# bldc-driver.net
KiCad netlist of a schematic drawn in Altium Designer
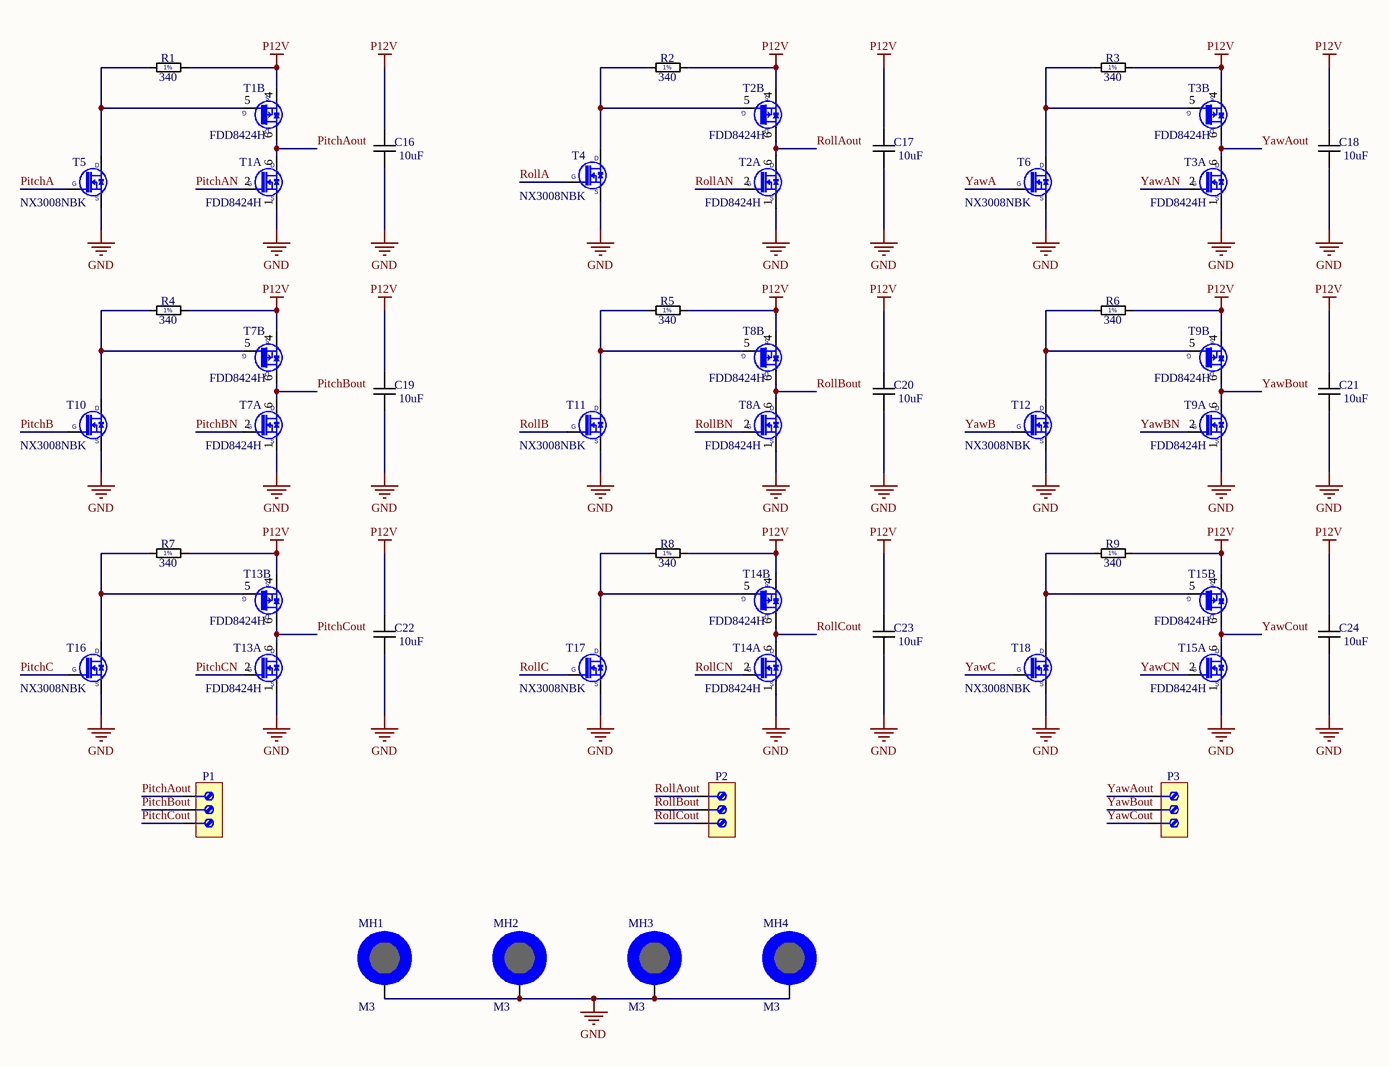
[diagram p0: bldc-driver.SchDoc]

(export (version "E")
  (design (tool "Eeschema 10.0.6"))
  (components
    (comp (ref "C16")
      (value "10uF")
      (footprint "CAPC0603X90N")
      (description "Non-polarised capacitor")
      (fields
        (field (name "MANUFACTURER") "GENERIC")
        (field (name "MANUFACTURER PART NUMBER") "CC0603_10UF_16V_20%_X5R")
        (field (name "AUTHOR") "KB")
      )
      (libsource (lib "Capacitors") (part "Capacitor - non polarized"))
    )
    (comp (ref "C17")
      (value "10uF")
      (footprint "CAPC0603X90N")
      (description "Non-polarised capacitor")
      (fields
        (field (name "MANUFACTURER") "GENERIC")
        (field (name "MANUFACTURER PART NUMBER") "CC0603_10UF_16V_20%_X5R")
        (field (name "AUTHOR") "KB")
      )
      (libsource (lib "Capacitors") (part "Capacitor - non polarized"))
    )
    (comp (ref "C18")
      (value "10uF")
      (footprint "CAPC0603X90N")
      (description "Non-polarised capacitor")
      (fields
        (field (name "MANUFACTURER") "GENERIC")
        (field (name "MANUFACTURER PART NUMBER") "CC0603_10UF_16V_20%_X5R")
        (field (name "AUTHOR") "KB")
      )
      (libsource (lib "Capacitors") (part "Capacitor - non polarized"))
    )
    (comp (ref "C19")
      (value "10uF")
      (footprint "CAPC0603X90N")
      (description "Non-polarised capacitor")
      (fields
        (field (name "MANUFACTURER") "GENERIC")
        (field (name "MANUFACTURER PART NUMBER") "CC0603_10UF_16V_20%_X5R")
        (field (name "AUTHOR") "KB")
      )
      (libsource (lib "Capacitors") (part "Capacitor - non polarized"))
    )
    (comp (ref "C20")
      (value "10uF")
      (footprint "CAPC0603X90N")
      (description "Non-polarised capacitor")
      (fields
        (field (name "MANUFACTURER") "GENERIC")
        (field (name "MANUFACTURER PART NUMBER") "CC0603_10UF_16V_20%_X5R")
        (field (name "AUTHOR") "KB")
      )
      (libsource (lib "Capacitors") (part "Capacitor - non polarized"))
    )
    (comp (ref "C21")
      (value "10uF")
      (footprint "CAPC0603X90N")
      (description "Non-polarised capacitor")
      (fields
        (field (name "MANUFACTURER") "GENERIC")
        (field (name "MANUFACTURER PART NUMBER") "CC0603_10UF_16V_20%_X5R")
        (field (name "AUTHOR") "KB")
      )
      (libsource (lib "Capacitors") (part "Capacitor - non polarized"))
    )
    (comp (ref "C22")
      (value "10uF")
      (footprint "CAPC0603X90N")
      (description "Non-polarised capacitor")
      (fields
        (field (name "MANUFACTURER") "GENERIC")
        (field (name "MANUFACTURER PART NUMBER") "CC0603_10UF_16V_20%_X5R")
        (field (name "AUTHOR") "KB")
      )
      (libsource (lib "Capacitors") (part "Capacitor - non polarized"))
    )
    (comp (ref "C23")
      (value "10uF")
      (footprint "CAPC0603X90N")
      (description "Non-polarised capacitor")
      (fields
        (field (name "MANUFACTURER") "GENERIC")
        (field (name "MANUFACTURER PART NUMBER") "CC0603_10UF_16V_20%_X5R")
        (field (name "AUTHOR") "KB")
      )
      (libsource (lib "Capacitors") (part "Capacitor - non polarized"))
    )
    (comp (ref "C24")
      (value "10uF")
      (footprint "CAPC0603X90N")
      (description "Non-polarised capacitor")
      (fields
        (field (name "MANUFACTURER") "GENERIC")
        (field (name "MANUFACTURER PART NUMBER") "CC0603_10UF_16V_20%_X5R")
        (field (name "AUTHOR") "KB")
      )
      (libsource (lib "Capacitors") (part "Capacitor - non polarized"))
    )
    (comp (ref "MH1")
      (value "M3")
      (footprint "MH-M3_COPPER")
      (description "Mounting hole, M3, exposed pad")
      (fields (field (name "AUTHOR") "KB"))
      (libsource (lib "Mechanical And PCB Features") (part "MH"))
    )
    (comp (ref "MH2")
      (value "M3")
      (footprint "MH-M3_COPPER")
      (description "Mounting hole, M3, exposed pad")
      (fields (field (name "AUTHOR") "KB"))
      (libsource (lib "Mechanical And PCB Features") (part "MH"))
    )
    (comp (ref "MH3")
      (value "M3")
      (footprint "MH-M3_COPPER")
      (description "Mounting hole, M3, exposed pad")
      (fields (field (name "AUTHOR") "KB"))
      (libsource (lib "Mechanical And PCB Features") (part "MH"))
    )
    (comp (ref "MH4")
      (value "M3")
      (footprint "MH-M3_COPPER")
      (description "Mounting hole, M3, exposed pad")
      (fields (field (name "AUTHOR") "KB"))
      (libsource (lib "Mechanical And PCB Features") (part "MH"))
    )
    (comp (ref "P1")
      (value "AK100/..DS-5.0-V-GREY")
      (footprint "SCREWERM_THT_3X1H_5P08MM")
      (description "Terminal Block, Right angle, 3 Positions, THT, Screw Connection, 15x9mm body")
      (fields
        (field (name "MANUFACTURER") "GENERIC")
        (field (name "MANUFACTURER PART NUMBER") "SCREWTERM_THT_3X1H_5P08MM")
        (field (name "AUTHOR") "KB")
      )
      (libsource (lib "Connectors") (part "Terminal Block_3 Positions_Screw Connection"))
    )
    (comp (ref "P2")
      (value "AK100/..DS-5.0-V-GREY")
      (footprint "SCREWERM_THT_3X1H_5P08MM")
      (description "Terminal Block, Right angle, 3 Positions, THT, Screw Connection, 15x9mm body")
      (fields
        (field (name "MANUFACTURER") "GENERIC")
        (field (name "MANUFACTURER PART NUMBER") "SCREWTERM_THT_3X1H_5P08MM")
        (field (name "AUTHOR") "KB")
      )
      (libsource (lib "Connectors") (part "Terminal Block_3 Positions_Screw Connection"))
    )
    (comp (ref "P3")
      (value "AK100/..DS-5.0-V-GREY")
      (footprint "SCREWERM_THT_3X1H_5P08MM")
      (description "Terminal Block, Right angle, 3 Positions, THT, Screw Connection, 15x9mm body")
      (fields
        (field (name "MANUFACTURER") "GENERIC")
        (field (name "MANUFACTURER PART NUMBER") "SCREWTERM_THT_3X1H_5P08MM")
        (field (name "AUTHOR") "KB")
      )
      (libsource (lib "Connectors") (part "Terminal Block_3 Positions_Screw Connection"))
    )
    (comp (ref "R1")
      (value "340")
      (footprint "RESC0402X40N")
      (description "General Purpose Thick Film Chip Resistor")
      (fields
        (field (name "MANUFACTURER") "GENERIC")
        (field (name "MANUFACTURER PART NUMBER") "R0402_340R_0.0625W 0.1W 0.125W 0.25W 0.5W 1W 0.75W 1W_100PPM")
        (field (name "AUTHOR") "KB")
      )
      (libsource (lib "Resistors") (part "Resistor - 1%"))
    )
    (comp (ref "R2")
      (value "340")
      (footprint "RESC0402X40N")
      (description "General Purpose Thick Film Chip Resistor")
      (fields
        (field (name "MANUFACTURER") "GENERIC")
        (field (name "MANUFACTURER PART NUMBER") "R0402_340R_0.0625W 0.1W 0.125W 0.25W 0.5W 1W 0.75W 1W_100PPM")
        (field (name "AUTHOR") "KB")
      )
      (libsource (lib "Resistors") (part "Resistor - 1%"))
    )
    (comp (ref "R3")
      (value "340")
      (footprint "RESC0402X40N")
      (description "General Purpose Thick Film Chip Resistor")
      (fields
        (field (name "MANUFACTURER") "GENERIC")
        (field (name "MANUFACTURER PART NUMBER") "R0402_340R_0.0625W 0.1W 0.125W 0.25W 0.5W 1W 0.75W 1W_100PPM")
        (field (name "AUTHOR") "KB")
      )
      (libsource (lib "Resistors") (part "Resistor - 1%"))
    )
    (comp (ref "R4")
      (value "340")
      (footprint "RESC0402X40N")
      (description "General Purpose Thick Film Chip Resistor")
      (fields
        (field (name "MANUFACTURER") "GENERIC")
        (field (name "MANUFACTURER PART NUMBER") "R0402_340R_0.0625W 0.1W 0.125W 0.25W 0.5W 1W 0.75W 1W_100PPM")
        (field (name "AUTHOR") "KB")
      )
      (libsource (lib "Resistors") (part "Resistor - 1%"))
    )
    (comp (ref "R5")
      (value "340")
      (footprint "RESC0402X40N")
      (description "General Purpose Thick Film Chip Resistor")
      (fields
        (field (name "MANUFACTURER") "GENERIC")
        (field (name "MANUFACTURER PART NUMBER") "R0402_340R_0.0625W 0.1W 0.125W 0.25W 0.5W 1W 0.75W 1W_100PPM")
        (field (name "AUTHOR") "KB")
      )
      (libsource (lib "Resistors") (part "Resistor - 1%"))
    )
    (comp (ref "R6")
      (value "340")
      (footprint "RESC0402X40N")
      (description "General Purpose Thick Film Chip Resistor")
      (fields
        (field (name "MANUFACTURER") "GENERIC")
        (field (name "MANUFACTURER PART NUMBER") "R0402_340R_0.0625W 0.1W 0.125W 0.25W 0.5W 1W 0.75W 1W_100PPM")
        (field (name "AUTHOR") "KB")
      )
      (libsource (lib "Resistors") (part "Resistor - 1%"))
    )
    (comp (ref "R7")
      (value "340")
      (footprint "RESC0402X40N")
      (description "General Purpose Thick Film Chip Resistor")
      (fields
        (field (name "MANUFACTURER") "GENERIC")
        (field (name "MANUFACTURER PART NUMBER") "R0402_340R_0.0625W 0.1W 0.125W 0.25W 0.5W 1W 0.75W 1W_100PPM")
        (field (name "AUTHOR") "KB")
      )
      (libsource (lib "Resistors") (part "Resistor - 1%"))
    )
    (comp (ref "R8")
      (value "340")
      (footprint "RESC0402X40N")
      (description "General Purpose Thick Film Chip Resistor")
      (fields
        (field (name "MANUFACTURER") "GENERIC")
        (field (name "MANUFACTURER PART NUMBER") "R0402_340R_0.0625W 0.1W 0.125W 0.25W 0.5W 1W 0.75W 1W_100PPM")
        (field (name "AUTHOR") "KB")
      )
      (libsource (lib "Resistors") (part "Resistor - 1%"))
    )
    (comp (ref "R9")
      (value "340")
      (footprint "RESC0402X40N")
      (description "General Purpose Thick Film Chip Resistor")
      (fields
        (field (name "MANUFACTURER") "GENERIC")
        (field (name "MANUFACTURER PART NUMBER") "R0402_340R_0.0625W 0.1W 0.125W 0.25W 0.5W 1W 0.75W 1W_100PPM")
        (field (name "AUTHOR") "KB")
      )
      (libsource (lib "Resistors") (part "Resistor - 1%"))
    )
    (comp (ref "T1")
      (value "FDD8424H")
      (footprint "TO252 - 4L")
      (fields (field (name "AUTHOR") "PC"))
      (libsource (lib "ICs And Semiconductors") (part "FDD8424H"))
    )
    (comp (ref "T2")
      (value "FDD8424H")
      (footprint "TO252 - 4L")
      (fields (field (name "AUTHOR") "PC"))
      (libsource (lib "ICs And Semiconductors") (part "FDD8424H"))
    )
    (comp (ref "T3")
      (value "FDD8424H")
      (footprint "TO252 - 4L")
      (fields (field (name "AUTHOR") "PC"))
      (libsource (lib "") (part "FDD8424H_1"))
    )
    (comp (ref "T4")
      (value "NX3008NBK")
      (footprint "SOT23-3")
      (description "30 V, 400 mA N-channel Trench MOSFET")
      (fields (field (name "AUTHOR") "PC"))
      (libsource (lib "ICs And Semiconductors") (part "N-MOSFET-D 1G 2S 3D"))
    )
    (comp (ref "T5")
      (value "NX3008NBK")
      (footprint "SOT23-3")
      (description "30 V, 400 mA N-channel Trench MOSFET")
      (fields (field (name "AUTHOR") "PC"))
      (libsource (lib "ICs And Semiconductors") (part "N-MOSFET-D 1G 2S 3D"))
    )
    (comp (ref "T6")
      (value "NX3008NBK")
      (footprint "SOT23-3")
      (description "30 V, 400 mA N-channel Trench MOSFET")
      (fields (field (name "AUTHOR") "PC"))
      (libsource (lib "ICs And Semiconductors") (part "N-MOSFET-D 1G 2S 3D"))
    )
    (comp (ref "T7")
      (value "FDD8424H")
      (footprint "TO252 - 4L")
      (fields (field (name "AUTHOR") "PC"))
      (libsource (lib "ICs And Semiconductors") (part "FDD8424H"))
    )
    (comp (ref "T8")
      (value "FDD8424H")
      (footprint "TO252 - 4L")
      (fields (field (name "AUTHOR") "PC"))
      (libsource (lib "ICs And Semiconductors") (part "FDD8424H"))
    )
    (comp (ref "T9")
      (value "FDD8424H")
      (footprint "TO252 - 4L")
      (fields (field (name "AUTHOR") "PC"))
      (libsource (lib "") (part "FDD8424H_1"))
    )
    (comp (ref "T10")
      (value "NX3008NBK")
      (footprint "SOT23-3")
      (description "30 V, 400 mA N-channel Trench MOSFET")
      (fields (field (name "AUTHOR") "PC"))
      (libsource (lib "ICs And Semiconductors") (part "N-MOSFET-D 1G 2S 3D"))
    )
    (comp (ref "T11")
      (value "NX3008NBK")
      (footprint "SOT23-3")
      (description "30 V, 400 mA N-channel Trench MOSFET")
      (fields (field (name "AUTHOR") "PC"))
      (libsource (lib "ICs And Semiconductors") (part "N-MOSFET-D 1G 2S 3D"))
    )
    (comp (ref "T12")
      (value "NX3008NBK")
      (footprint "SOT23-3")
      (description "30 V, 400 mA N-channel Trench MOSFET")
      (fields (field (name "AUTHOR") "PC"))
      (libsource (lib "ICs And Semiconductors") (part "N-MOSFET-D 1G 2S 3D"))
    )
    (comp (ref "T13")
      (value "FDD8424H")
      (footprint "TO252 - 4L")
      (fields (field (name "AUTHOR") "PC"))
      (libsource (lib "ICs And Semiconductors") (part "FDD8424H"))
    )
    (comp (ref "T14")
      (value "FDD8424H")
      (footprint "TO252 - 4L")
      (fields (field (name "AUTHOR") "PC"))
      (libsource (lib "") (part "FDD8424H_1"))
    )
    (comp (ref "T15")
      (value "FDD8424H")
      (footprint "TO252 - 4L")
      (fields (field (name "AUTHOR") "PC"))
      (libsource (lib "ICs And Semiconductors") (part "FDD8424H"))
    )
    (comp (ref "T16")
      (value "NX3008NBK")
      (footprint "SOT23-3")
      (description "30 V, 400 mA N-channel Trench MOSFET")
      (fields (field (name "AUTHOR") "PC"))
      (libsource (lib "ICs And Semiconductors") (part "N-MOSFET-D 1G 2S 3D"))
    )
    (comp (ref "T17")
      (value "NX3008NBK")
      (footprint "SOT23-3")
      (description "30 V, 400 mA N-channel Trench MOSFET")
      (fields (field (name "AUTHOR") "PC"))
      (libsource (lib "ICs And Semiconductors") (part "N-MOSFET-D 1G 2S 3D"))
    )
    (comp (ref "T18")
      (value "NX3008NBK")
      (footprint "SOT23-3")
      (description "30 V, 400 mA N-channel Trench MOSFET")
      (fields (field (name "AUTHOR") "PC"))
      (libsource (lib "ICs And Semiconductors") (part "N-MOSFET-D 1G 2S 3D"))
    )
  )
  (nets
    (net (code "1") (name "/PitchA") (class "Default")
      (node (ref "T5") (pin "1") (pinfunction "G_1") (pintype "passive"))
    )
    (net (code "2") (name "/PitchAN") (class "Default")
      (node (ref "T1") (pin "2") (pinfunction "G_2") (pintype "passive"))
    )
    (net (code "3") (name "/PitchAout") (class "Default")
      (node (ref "P1") (pin "1") (pinfunction "1_1") (pintype "passive"))
      (node (ref "T1") (pin "6") (pinfunction "D_6") (pintype "passive"))
    )
    (net (code "4") (name "/PitchB") (class "Default")
      (node (ref "T10") (pin "1") (pinfunction "G_1") (pintype "passive"))
    )
    (net (code "5") (name "/PitchBN") (class "Default")
      (node (ref "T7") (pin "2") (pinfunction "G_2") (pintype "passive"))
    )
    (net (code "6") (name "/PitchBout") (class "Default")
      (node (ref "P1") (pin "2") (pinfunction "2_2") (pintype "passive"))
      (node (ref "T7") (pin "6") (pinfunction "D_6") (pintype "passive"))
    )
    (net (code "7") (name "/PitchC") (class "Default")
      (node (ref "T16") (pin "1") (pinfunction "G_1") (pintype "passive"))
    )
    (net (code "8") (name "/PitchCN") (class "Default")
      (node (ref "T13") (pin "2") (pinfunction "G_2") (pintype "passive"))
    )
    (net (code "9") (name "/PitchCout") (class "Default")
      (node (ref "P1") (pin "3") (pinfunction "3_3") (pintype "passive"))
      (node (ref "T13") (pin "6") (pinfunction "D_6") (pintype "passive"))
    )
    (net (code "10") (name "/RollA") (class "Default")
      (node (ref "T4") (pin "1") (pinfunction "G_1") (pintype "passive"))
    )
    (net (code "11") (name "/RollAN") (class "Default")
      (node (ref "T2") (pin "2") (pinfunction "G_2") (pintype "passive"))
    )
    (net (code "12") (name "/RollAout") (class "Default")
      (node (ref "P2") (pin "1") (pinfunction "1_1") (pintype "passive"))
      (node (ref "T2") (pin "6") (pinfunction "D_6") (pintype "passive"))
    )
    (net (code "13") (name "/RollB") (class "Default")
      (node (ref "T11") (pin "1") (pinfunction "G_1") (pintype "passive"))
    )
    (net (code "14") (name "/RollBN") (class "Default")
      (node (ref "T8") (pin "2") (pinfunction "G_2") (pintype "passive"))
    )
    (net (code "15") (name "/RollBout") (class "Default")
      (node (ref "P2") (pin "2") (pinfunction "2_2") (pintype "passive"))
      (node (ref "T8") (pin "6") (pinfunction "D_6") (pintype "passive"))
    )
    (net (code "16") (name "/RollC") (class "Default")
      (node (ref "T17") (pin "1") (pinfunction "G_1") (pintype "passive"))
    )
    (net (code "17") (name "/RollCN") (class "Default")
      (node (ref "T14") (pin "2") (pinfunction "G_2") (pintype "passive"))
    )
    (net (code "18") (name "/RollCout") (class "Default")
      (node (ref "P2") (pin "3") (pinfunction "3_3") (pintype "passive"))
      (node (ref "T14") (pin "6") (pinfunction "D_6") (pintype "passive"))
    )
    (net (code "19") (name "/YawA") (class "Default")
      (node (ref "T6") (pin "1") (pinfunction "G_1") (pintype "passive"))
    )
    (net (code "20") (name "/YawAN") (class "Default")
      (node (ref "T3") (pin "2") (pinfunction "G_2") (pintype "passive"))
    )
    (net (code "21") (name "/YawAout") (class "Default")
      (node (ref "P3") (pin "1") (pinfunction "1_1") (pintype "passive"))
      (node (ref "T3") (pin "6") (pinfunction "D_6") (pintype "passive"))
    )
    (net (code "22") (name "/YawB") (class "Default")
      (node (ref "T12") (pin "1") (pinfunction "G_1") (pintype "passive"))
    )
    (net (code "23") (name "/YawBN") (class "Default")
      (node (ref "T9") (pin "2") (pinfunction "G_2") (pintype "passive"))
    )
    (net (code "24") (name "/YawBout") (class "Default")
      (node (ref "P3") (pin "2") (pinfunction "2_2") (pintype "passive"))
      (node (ref "T9") (pin "6") (pinfunction "D_6") (pintype "passive"))
    )
    (net (code "25") (name "/YawC") (class "Default")
      (node (ref "T18") (pin "1") (pinfunction "G_1") (pintype "passive"))
    )
    (net (code "26") (name "/YawCN") (class "Default")
      (node (ref "T15") (pin "2") (pinfunction "G_2") (pintype "passive"))
    )
    (net (code "27") (name "/YawCout") (class "Default")
      (node (ref "P3") (pin "3") (pinfunction "3_3") (pintype "passive"))
      (node (ref "T15") (pin "6") (pinfunction "D_6") (pintype "passive"))
    )
    (net (code "28") (name "GND") (class "Default")
      (node (ref "C16") (pin "1") (pinfunction "1_1") (pintype "passive"))
      (node (ref "C17") (pin "1") (pinfunction "1_1") (pintype "passive"))
      (node (ref "C18") (pin "1") (pinfunction "1_1") (pintype "passive"))
      (node (ref "C19") (pin "1") (pinfunction "1_1") (pintype "passive"))
      (node (ref "C20") (pin "1") (pinfunction "1_1") (pintype "passive"))
      (node (ref "C21") (pin "1") (pinfunction "1_1") (pintype "passive"))
      (node (ref "C22") (pin "1") (pinfunction "1_1") (pintype "passive"))
      (node (ref "C23") (pin "1") (pinfunction "1_1") (pintype "passive"))
      (node (ref "C24") (pin "1") (pinfunction "1_1") (pintype "passive"))
      (node (ref "MH1") (pin "MH") (pinfunction "MH_MH") (pintype "passive"))
      (node (ref "MH2") (pin "MH") (pinfunction "MH_MH") (pintype "passive"))
      (node (ref "MH3") (pin "MH") (pinfunction "MH_MH") (pintype "passive"))
      (node (ref "MH4") (pin "MH") (pinfunction "MH_MH") (pintype "passive"))
      (node (ref "T1") (pin "1") (pinfunction "S_1") (pintype "passive"))
      (node (ref "T10") (pin "2") (pinfunction "S_2") (pintype "passive"))
      (node (ref "T11") (pin "2") (pinfunction "S_2") (pintype "passive"))
      (node (ref "T12") (pin "2") (pinfunction "S_2") (pintype "passive"))
      (node (ref "T13") (pin "1") (pinfunction "S_1") (pintype "passive"))
      (node (ref "T14") (pin "1") (pinfunction "S_1") (pintype "passive"))
      (node (ref "T15") (pin "1") (pinfunction "S_1") (pintype "passive"))
      (node (ref "T16") (pin "2") (pinfunction "S_2") (pintype "passive"))
      (node (ref "T17") (pin "2") (pinfunction "S_2") (pintype "passive"))
      (node (ref "T18") (pin "2") (pinfunction "S_2") (pintype "passive"))
      (node (ref "T2") (pin "1") (pinfunction "S_1") (pintype "passive"))
      (node (ref "T3") (pin "1") (pinfunction "S_1") (pintype "passive"))
      (node (ref "T4") (pin "2") (pinfunction "S_2") (pintype "passive"))
      (node (ref "T5") (pin "2") (pinfunction "S_2") (pintype "passive"))
      (node (ref "T6") (pin "2") (pinfunction "S_2") (pintype "passive"))
      (node (ref "T7") (pin "1") (pinfunction "S_1") (pintype "passive"))
      (node (ref "T8") (pin "1") (pinfunction "S_1") (pintype "passive"))
      (node (ref "T9") (pin "1") (pinfunction "S_1") (pintype "passive"))
    )
    (net (code "29") (name "Net-(T1B-G)") (class "Default")
      (node (ref "R1") (pin "1") (pinfunction "1_1") (pintype "passive"))
      (node (ref "T1") (pin "5") (pinfunction "G_5") (pintype "passive"))
      (node (ref "T5") (pin "3") (pinfunction "D_3") (pintype "passive"))
    )
    (net (code "30") (name "Net-(T2B-G)") (class "Default")
      (node (ref "R2") (pin "1") (pinfunction "1_1") (pintype "passive"))
      (node (ref "T2") (pin "5") (pinfunction "G_5") (pintype "passive"))
      (node (ref "T4") (pin "3") (pinfunction "D_3") (pintype "passive"))
    )
    (net (code "31") (name "Net-(T3B-G)") (class "Default")
      (node (ref "R3") (pin "1") (pinfunction "1_1") (pintype "passive"))
      (node (ref "T3") (pin "5") (pinfunction "G_5") (pintype "passive"))
      (node (ref "T6") (pin "3") (pinfunction "D_3") (pintype "passive"))
    )
    (net (code "32") (name "Net-(T10-D)") (class "Default")
      (node (ref "R4") (pin "1") (pinfunction "1_1") (pintype "passive"))
      (node (ref "T10") (pin "3") (pinfunction "D_3") (pintype "passive"))
      (node (ref "T7") (pin "5") (pinfunction "G_5") (pintype "passive"))
    )
    (net (code "33") (name "Net-(T11-D)") (class "Default")
      (node (ref "R5") (pin "1") (pinfunction "1_1") (pintype "passive"))
      (node (ref "T11") (pin "3") (pinfunction "D_3") (pintype "passive"))
      (node (ref "T8") (pin "5") (pinfunction "G_5") (pintype "passive"))
    )
    (net (code "34") (name "Net-(T12-D)") (class "Default")
      (node (ref "R6") (pin "1") (pinfunction "1_1") (pintype "passive"))
      (node (ref "T12") (pin "3") (pinfunction "D_3") (pintype "passive"))
      (node (ref "T9") (pin "5") (pinfunction "G_5") (pintype "passive"))
    )
    (net (code "35") (name "Net-(T13B-G)") (class "Default")
      (node (ref "R7") (pin "1") (pinfunction "1_1") (pintype "passive"))
      (node (ref "T13") (pin "5") (pinfunction "G_5") (pintype "passive"))
      (node (ref "T16") (pin "3") (pinfunction "D_3") (pintype "passive"))
    )
    (net (code "36") (name "Net-(T14B-G)") (class "Default")
      (node (ref "R8") (pin "1") (pinfunction "1_1") (pintype "passive"))
      (node (ref "T14") (pin "5") (pinfunction "G_5") (pintype "passive"))
      (node (ref "T17") (pin "3") (pinfunction "D_3") (pintype "passive"))
    )
    (net (code "37") (name "Net-(T15B-G)") (class "Default")
      (node (ref "R9") (pin "1") (pinfunction "1_1") (pintype "passive"))
      (node (ref "T15") (pin "5") (pinfunction "G_5") (pintype "passive"))
      (node (ref "T18") (pin "3") (pinfunction "D_3") (pintype "passive"))
    )
    (net (code "38") (name "P12V") (class "Default")
      (node (ref "C16") (pin "2") (pinfunction "2_2") (pintype "passive"))
      (node (ref "C17") (pin "2") (pinfunction "2_2") (pintype "passive"))
      (node (ref "C18") (pin "2") (pinfunction "2_2") (pintype "passive"))
      (node (ref "C19") (pin "2") (pinfunction "2_2") (pintype "passive"))
      (node (ref "C20") (pin "2") (pinfunction "2_2") (pintype "passive"))
      (node (ref "C21") (pin "2") (pinfunction "2_2") (pintype "passive"))
      (node (ref "C22") (pin "2") (pinfunction "2_2") (pintype "passive"))
      (node (ref "C23") (pin "2") (pinfunction "2_2") (pintype "passive"))
      (node (ref "C24") (pin "2") (pinfunction "2_2") (pintype "passive"))
      (node (ref "R1") (pin "2") (pinfunction "2_2") (pintype "passive"))
      (node (ref "R2") (pin "2") (pinfunction "2_2") (pintype "passive"))
      (node (ref "R3") (pin "2") (pinfunction "2_2") (pintype "passive"))
      (node (ref "R4") (pin "2") (pinfunction "2_2") (pintype "passive"))
      (node (ref "R5") (pin "2") (pinfunction "2_2") (pintype "passive"))
      (node (ref "R6") (pin "2") (pinfunction "2_2") (pintype "passive"))
      (node (ref "R7") (pin "2") (pinfunction "2_2") (pintype "passive"))
      (node (ref "R8") (pin "2") (pinfunction "2_2") (pintype "passive"))
      (node (ref "R9") (pin "2") (pinfunction "2_2") (pintype "passive"))
      (node (ref "T1") (pin "4") (pinfunction "S_4") (pintype "passive"))
      (node (ref "T13") (pin "4") (pinfunction "S_4") (pintype "passive"))
      (node (ref "T14") (pin "4") (pinfunction "S_4") (pintype "passive"))
      (node (ref "T15") (pin "4") (pinfunction "S_4") (pintype "passive"))
      (node (ref "T2") (pin "4") (pinfunction "S_4") (pintype "passive"))
      (node (ref "T3") (pin "4") (pinfunction "S_4") (pintype "passive"))
      (node (ref "T7") (pin "4") (pinfunction "S_4") (pintype "passive"))
      (node (ref "T8") (pin "4") (pinfunction "S_4") (pintype "passive"))
      (node (ref "T9") (pin "4") (pinfunction "S_4") (pintype "passive"))
    )
  )
)
